# SPDTrelay_w_diodes.net
KiCad netlist of a schematic drawn in EAGLE
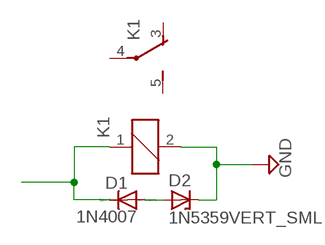
[diagram p0: schematic, sheet 1]

(export (version "E")
  (design (tool "Eeschema 10.0.6"))
  (components
    (comp (ref "D1")
      (value "1N4007")
      (footprint "eagle-import:RAD2,5")
      (libsource (lib "eagle-import") (part "1N4007"))
    )
    (comp (ref "D2")
      (value "1N5359VERT_SML")
      (footprint "eagle-import:RAD2.5_D2")
      (libsource (lib "eagle-import") (part "1N5359VERT_SML"))
    )
    (comp (ref "K1")
      (value "HF41F-12-Z")
      (footprint "eagle-import:HF41F-12-Z")
      (libsource (lib "eagle-import") (part "HF41F-12-Z"))
    )
  )
  (nets
    (net (code "1") (name "GND") (class "Default")
      (node (ref "D2") (pin "C") (pinfunction "C_C") (pintype "passive"))
      (node (ref "K1") (pin "2") (pinfunction "2_2") (pintype "passive"))
    )
    (net (code "2") (name "Net-(D1-PadA)") (class "Default")
      (node (ref "D1") (pin "A") (pinfunction "A_A") (pintype "passive"))
      (node (ref "D2") (pin "A") (pinfunction "A_A") (pintype "passive"))
    )
    (net (code "3") (name "Net-(D1-PadC)") (class "Default")
      (node (ref "D1") (pin "C") (pinfunction "C_C") (pintype "passive"))
      (node (ref "K1") (pin "1") (pinfunction "1_1") (pintype "passive"))
    )
    (net (code "4") (name "unconnected-(K1B-O-Pad3)") (class "Default")
      (node (ref "K1") (pin "3") (pinfunction "O_3") (pintype "passive"))
    )
    (net (code "5") (name "unconnected-(K1B-P-Pad4)") (class "Default")
      (node (ref "K1") (pin "4") (pinfunction "P_4") (pintype "passive"))
    )
    (net (code "6") (name "unconnected-(K1B-S-Pad5)") (class "Default")
      (node (ref "K1") (pin "5") (pinfunction "S_5") (pintype "passive"))
    )
  )
)
